# SCH_ESP32C3-haedtracker_2026-03-10.net
KiCad netlist of a schematic drawn in EasyEDA
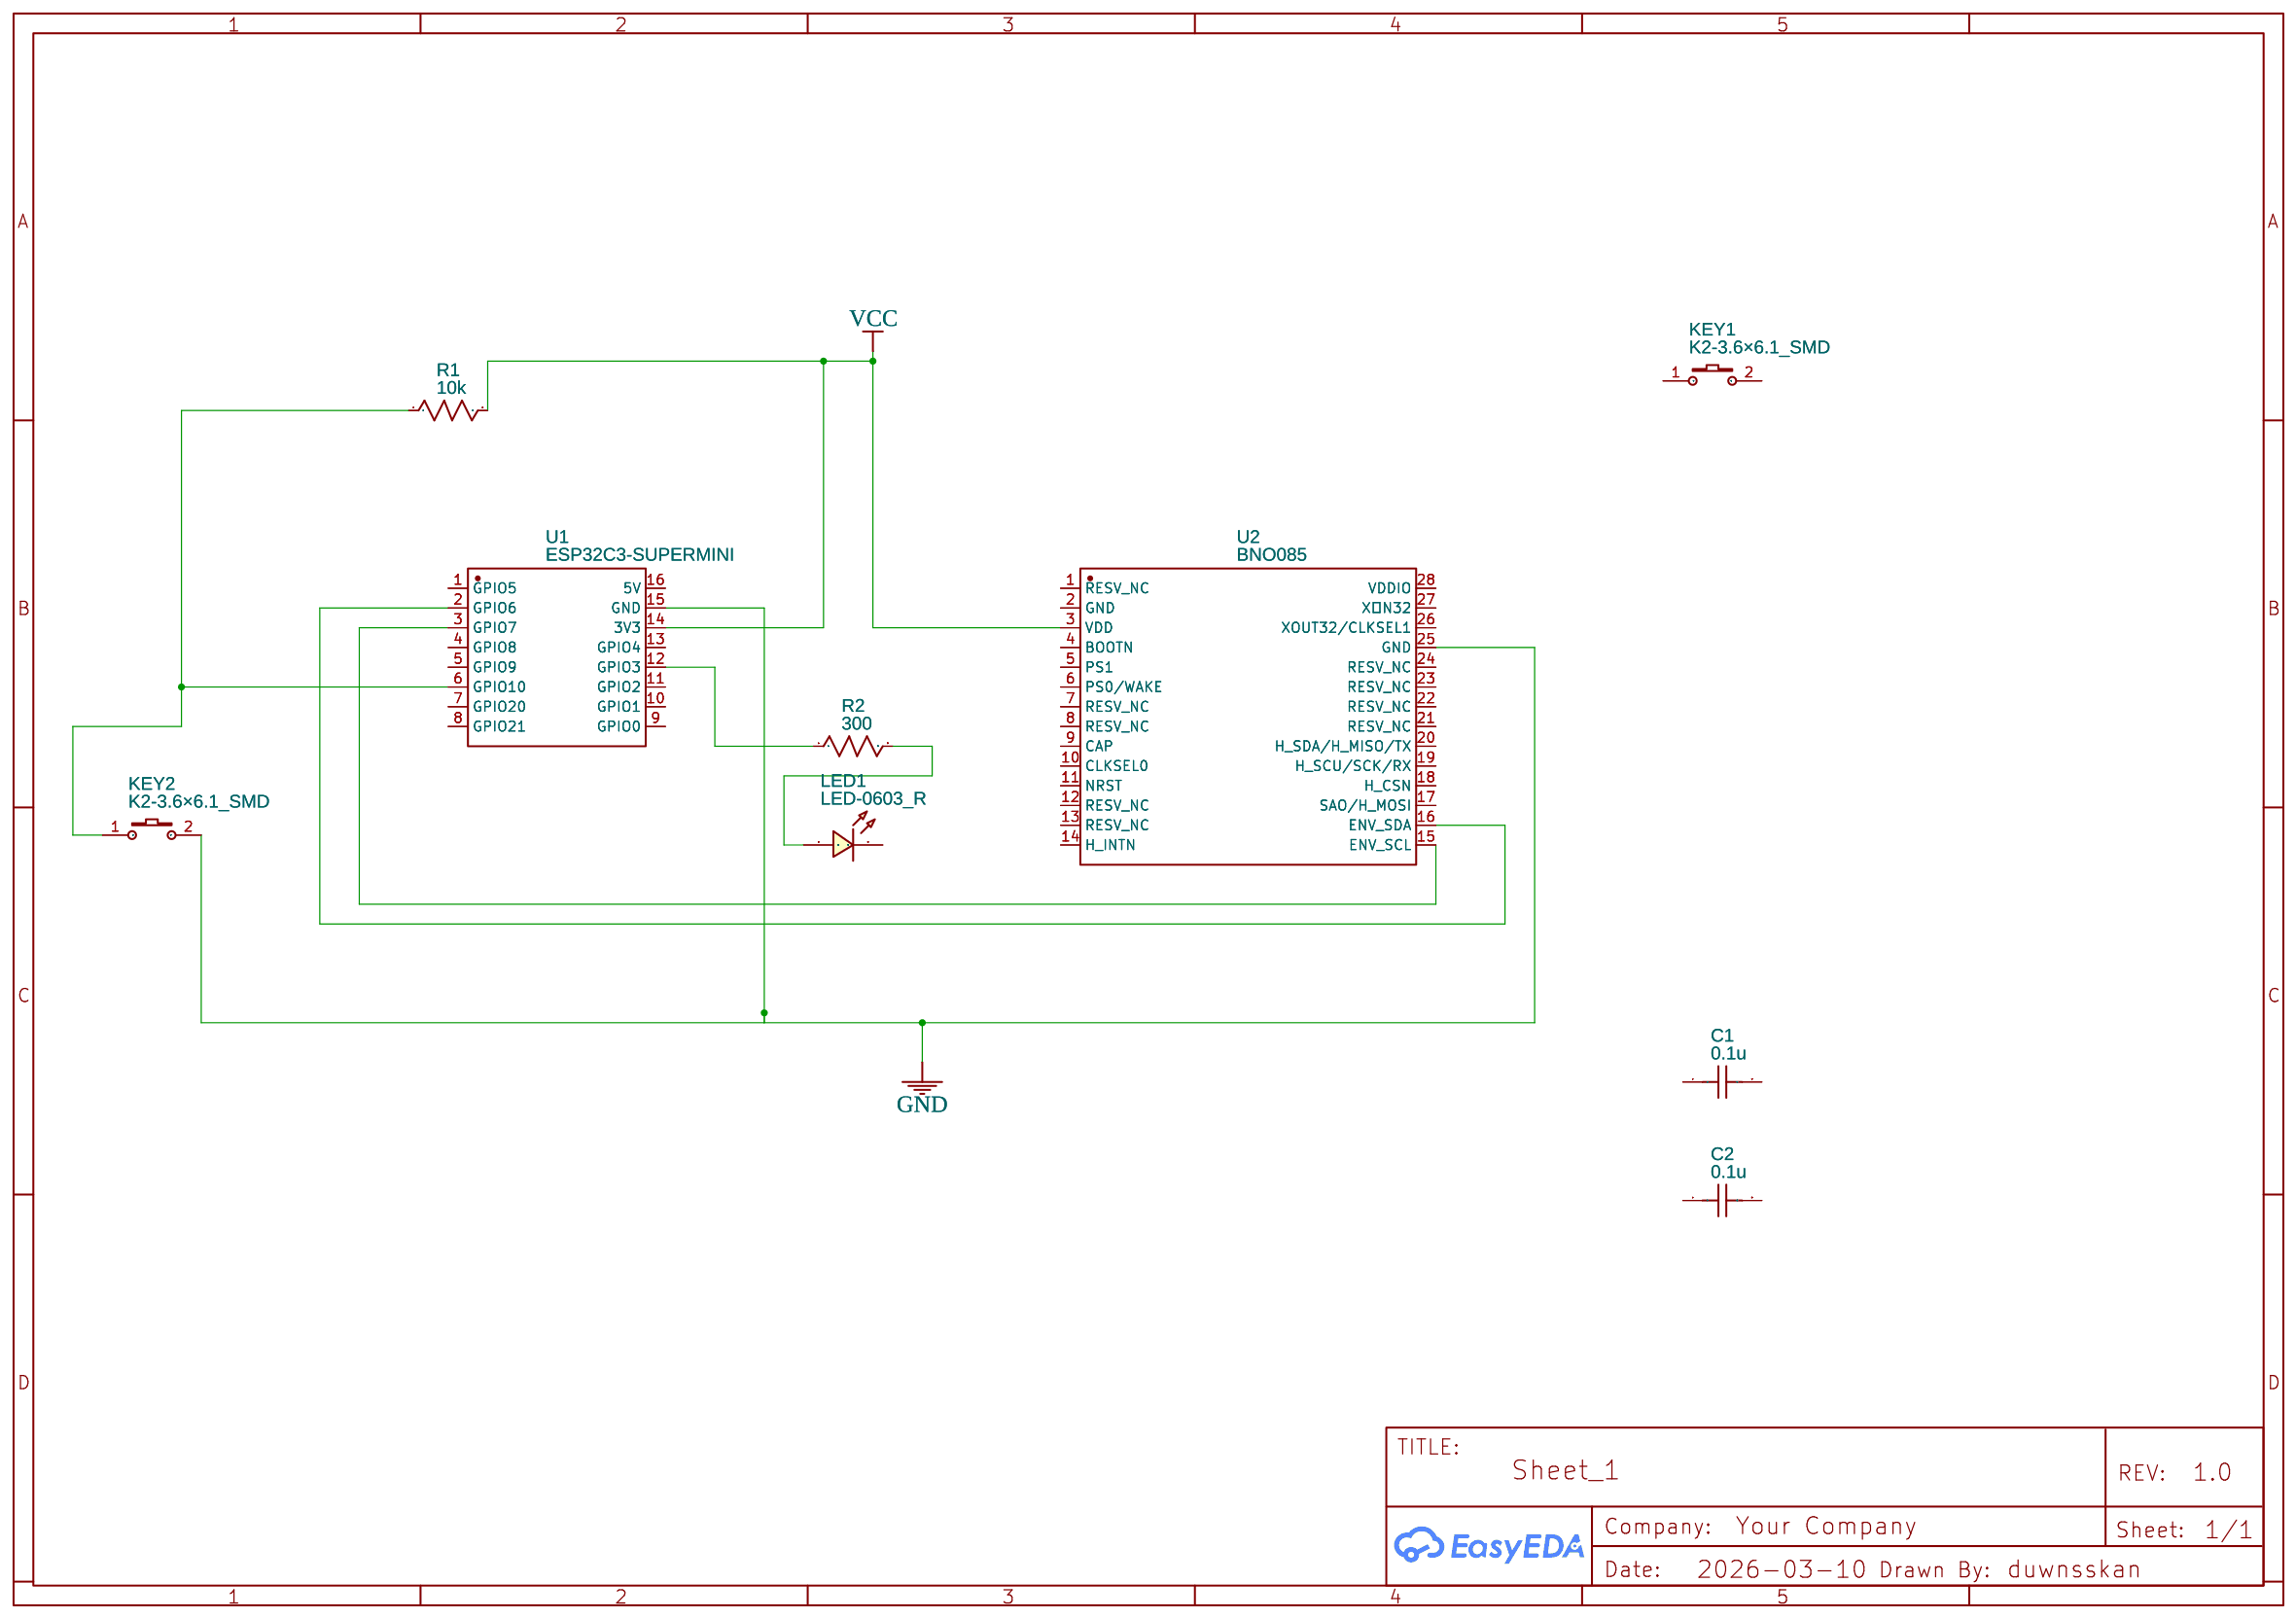
[diagram p0: schematic sheet]

(export (version "E")
  (design (tool "Eeschema 10.0.6"))
  (components
    (comp (ref "C1") (value "0.1u") (libsource (lib "") (part "C_0603_US")))
    (comp (ref "C2") (value "0.1u") (libsource (lib "") (part "C_0603_US")))
    (comp (ref "KEY1")
      (value "K2-3.6×6.1_SMD")
      (fields (field (name "Manufacturer Part") "K2-1107ST-A4SW-06"))
      (libsource (lib "") (part "K2-3.6×6.1_SMD"))
    )
    (comp (ref "KEY2")
      (value "K2-3.6×6.1_SMD")
      (fields (field (name "Manufacturer Part") "K2-1107ST-A4SW-06"))
      (libsource (lib "") (part "K2-3.6×6.1_SMD"))
    )
    (comp (ref "LED1")
      (value "LED-0603_R")
      (fields
        (field (name "Manufacturer Part") "19-217/R6C-AL1M2VY/3T")
        (field (name "Manufacturer") "EVERLIGHT(台湾亿光)")
      )
      (libsource (lib "") (part "LED-0603_R"))
    )
    (comp (ref "R1") (value "10k") (libsource (lib "") (part "R_0603_US")))
    (comp (ref "R2") (value "300") (libsource (lib "") (part "R_0603_US")))
    (comp (ref "U1")
      (value "ESP32C3-SUPERMINI")
      (fields (field (name "Manufacturer Part") "ESP32C3-SuperMini"))
      (libsource (lib "") (part "ESP32C3-SUPERMINI"))
    )
    (comp (ref "U2") (value "BNO085") (libsource (lib "") (part "BNO085")))
  )
  (nets
    (net (code "1") (name "GND") (class "Default")
      (node (ref "KEY2") (pin "2") (pinfunction "2_2") (pintype "unspecified"))
      (node (ref "U1") (pin "15") (pinfunction "GND_15") (pintype "unspecified"))
      (node (ref "U2") (pin "25") (pinfunction "GND_25") (pintype "unspecified"))
    )
    (net (code "2") (name "Net-(LED1-Pad1)") (class "Default")
      (node (ref "LED1") (pin "1") (pinfunction "1_1") (pintype "unspecified"))
      (node (ref "R2") (pin "2") (pinfunction "2_2") (pintype "unspecified"))
    )
    (net (code "3") (name "Net-(U1-GPIO3)") (class "Default")
      (node (ref "R2") (pin "1") (pinfunction "1_1") (pintype "unspecified"))
      (node (ref "U1") (pin "12") (pinfunction "GPIO3_12") (pintype "unspecified"))
    )
    (net (code "4") (name "Net-(U1-GPIO6)") (class "Default")
      (node (ref "U1") (pin "2") (pinfunction "GPIO6_2") (pintype "unspecified"))
      (node (ref "U2") (pin "16") (pinfunction "ENV_SDA_16") (pintype "unspecified"))
    )
    (net (code "5") (name "Net-(U1-GPIO7)") (class "Default")
      (node (ref "U1") (pin "3") (pinfunction "GPIO7_3") (pintype "unspecified"))
      (node (ref "U2") (pin "15") (pinfunction "ENV_SCL_15") (pintype "unspecified"))
    )
    (net (code "6") (name "Net-(U1-GPIO10)") (class "Default")
      (node (ref "KEY2") (pin "1") (pinfunction "1_1") (pintype "unspecified"))
      (node (ref "R1") (pin "1") (pinfunction "1_1") (pintype "unspecified"))
      (node (ref "U1") (pin "6") (pinfunction "GPIO10_6") (pintype "unspecified"))
    )
    (net (code "7") (name "VCC") (class "Default")
      (node (ref "R1") (pin "2") (pinfunction "2_2") (pintype "unspecified"))
      (node (ref "U1") (pin "14") (pinfunction "3V3_14") (pintype "unspecified"))
      (node (ref "U2") (pin "3") (pinfunction "VDD_3") (pintype "unspecified"))
    )
    (net (code "8") (name "unconnected-(C1-Pad1)") (class "Default")
      (node (ref "C1") (pin "1") (pinfunction "1_1") (pintype "unspecified"))
    )
    (net (code "9") (name "unconnected-(C1-Pad2)") (class "Default")
      (node (ref "C1") (pin "2") (pinfunction "2_2") (pintype "unspecified"))
    )
    (net (code "10") (name "unconnected-(C2-Pad1)") (class "Default")
      (node (ref "C2") (pin "1") (pinfunction "1_1") (pintype "unspecified"))
    )
    (net (code "11") (name "unconnected-(C2-Pad2)") (class "Default")
      (node (ref "C2") (pin "2") (pinfunction "2_2") (pintype "unspecified"))
    )
    (net (code "12") (name "unconnected-(KEY1-Pad1)") (class "Default")
      (node (ref "KEY1") (pin "1") (pinfunction "1_1") (pintype "unspecified"))
    )
    (net (code "13") (name "unconnected-(KEY1-Pad2)") (class "Default")
      (node (ref "KEY1") (pin "2") (pinfunction "2_2") (pintype "unspecified"))
    )
    (net (code "14") (name "unconnected-(LED1-Pad2)") (class "Default")
      (node (ref "LED1") (pin "2") (pinfunction "2_2") (pintype "unspecified"))
    )
    (net (code "15") (name "unconnected-(U1-5V-Pad16)") (class "Default")
      (node (ref "U1") (pin "16") (pinfunction "5V_16") (pintype "unspecified"))
    )
    (net (code "16") (name "unconnected-(U1-GPIO0-Pad9)") (class "Default")
      (node (ref "U1") (pin "9") (pinfunction "GPIO0_9") (pintype "unspecified"))
    )
    (net (code "17") (name "unconnected-(U1-GPIO1-Pad10)") (class "Default")
      (node (ref "U1") (pin "10") (pinfunction "GPIO1_10") (pintype "unspecified"))
    )
    (net (code "18") (name "unconnected-(U1-GPIO2-Pad11)") (class "Default")
      (node (ref "U1") (pin "11") (pinfunction "GPIO2_11") (pintype "unspecified"))
    )
    (net (code "19") (name "unconnected-(U1-GPIO4-Pad13)") (class "Default")
      (node (ref "U1") (pin "13") (pinfunction "GPIO4_13") (pintype "unspecified"))
    )
    (net (code "20") (name "unconnected-(U1-GPIO5-Pad1)") (class "Default")
      (node (ref "U1") (pin "1") (pinfunction "GPIO5_1") (pintype "unspecified"))
    )
    (net (code "21") (name "unconnected-(U1-GPIO8-Pad4)") (class "Default")
      (node (ref "U1") (pin "4") (pinfunction "GPIO8_4") (pintype "unspecified"))
    )
    (net (code "22") (name "unconnected-(U1-GPIO9-Pad5)") (class "Default")
      (node (ref "U1") (pin "5") (pinfunction "GPIO9_5") (pintype "unspecified"))
    )
    (net (code "23") (name "unconnected-(U1-GPIO20-Pad7)") (class "Default")
      (node (ref "U1") (pin "7") (pinfunction "GPIO20_7") (pintype "unspecified"))
    )
    (net (code "24") (name "unconnected-(U1-GPIO21-Pad8)") (class "Default")
      (node (ref "U1") (pin "8") (pinfunction "GPIO21_8") (pintype "unspecified"))
    )
    (net (code "25") (name "unconnected-(U2-BOOTN-Pad4)") (class "Default")
      (node (ref "U2") (pin "4") (pinfunction "BOOTN_4") (pintype "unspecified"))
    )
    (net (code "26") (name "unconnected-(U2-CAP-Pad9)") (class "Default")
      (node (ref "U2") (pin "9") (pinfunction "CAP_9") (pintype "unspecified"))
    )
    (net (code "27") (name "unconnected-(U2-CLKSEL0-Pad10)") (class "Default")
      (node (ref "U2") (pin "10") (pinfunction "CLKSEL0_10") (pintype "unspecified"))
    )
    (net (code "28") (name "unconnected-(U2-GND-Pad2)") (class "Default")
      (node (ref "U2") (pin "2") (pinfunction "GND_2") (pintype "unspecified"))
    )
    (net (code "29") (name "unconnected-(U2-H_CSN-Pad18)") (class "Default")
      (node (ref "U2") (pin "18") (pinfunction "H_CSN_18") (pintype "unspecified"))
    )
    (net (code "30") (name "unconnected-(U2-H_INTN-Pad14)") (class "Default")
      (node (ref "U2") (pin "14") (pinfunction "H_INTN_14") (pintype "unspecified"))
    )
    (net (code "31") (name "unconnected-(U2-H_SCU{slash}SCK{slash}RX-Pad19)") (class "Default")
      (node (ref "U2") (pin "19") (pinfunction "H_SCU/SCK/RX_19") (pintype "unspecified"))
    )
    (net (code "32") (name "unconnected-(U2-H_SDA{slash}H_MISO{slash}TX-Pad20)") (class "Default")
      (node (ref "U2") (pin "20") (pinfunction "H_SDA/H_MISO/TX_20") (pintype "unspecified"))
    )
    (net (code "33") (name "unconnected-(U2-NRST-Pad11)") (class "Default")
      (node (ref "U2") (pin "11") (pinfunction "NRST_11") (pintype "unspecified"))
    )
    (net (code "34") (name "unconnected-(U2-PS0{slash}WAKE-Pad6)") (class "Default")
      (node (ref "U2") (pin "6") (pinfunction "PS0/WAKE_6") (pintype "unspecified"))
    )
    (net (code "35") (name "unconnected-(U2-PS1-Pad5)") (class "Default")
      (node (ref "U2") (pin "5") (pinfunction "PS1_5") (pintype "unspecified"))
    )
    (net (code "36") (name "unconnected-(U2-RESV_NC-Pad1)") (class "Default")
      (node (ref "U2") (pin "1") (pinfunction "RESV_NC_1") (pintype "unspecified"))
    )
    (net (code "37") (name "unconnected-(U2-RESV_NC-Pad7)") (class "Default")
      (node (ref "U2") (pin "7") (pinfunction "RESV_NC_7") (pintype "unspecified"))
    )
    (net (code "38") (name "unconnected-(U2-RESV_NC-Pad8)") (class "Default")
      (node (ref "U2") (pin "8") (pinfunction "RESV_NC_8") (pintype "unspecified"))
    )
    (net (code "39") (name "unconnected-(U2-RESV_NC-Pad12)") (class "Default")
      (node (ref "U2") (pin "12") (pinfunction "RESV_NC_12") (pintype "unspecified"))
    )
    (net (code "40") (name "unconnected-(U2-RESV_NC-Pad13)") (class "Default")
      (node (ref "U2") (pin "13") (pinfunction "RESV_NC_13") (pintype "unspecified"))
    )
    (net (code "41") (name "unconnected-(U2-RESV_NC-Pad21)") (class "Default")
      (node (ref "U2") (pin "21") (pinfunction "RESV_NC_21") (pintype "unspecified"))
    )
    (net (code "42") (name "unconnected-(U2-RESV_NC-Pad22)") (class "Default")
      (node (ref "U2") (pin "22") (pinfunction "RESV_NC_22") (pintype "unspecified"))
    )
    (net (code "43") (name "unconnected-(U2-RESV_NC-Pad23)") (class "Default")
      (node (ref "U2") (pin "23") (pinfunction "RESV_NC_23") (pintype "unspecified"))
    )
    (net (code "44") (name "unconnected-(U2-RESV_NC-Pad24)") (class "Default")
      (node (ref "U2") (pin "24") (pinfunction "RESV_NC_24") (pintype "unspecified"))
    )
    (net (code "45") (name "unconnected-(U2-SAO{slash}H_MOSI-Pad17)") (class "Default")
      (node (ref "U2") (pin "17") (pinfunction "SAO/H_MOSI_17") (pintype "unspecified"))
    )
    (net (code "46") (name "unconnected-(U2-VDDIO-Pad28)") (class "Default")
      (node (ref "U2") (pin "28") (pinfunction "VDDIO_28") (pintype "unspecified"))
    )
    (net (code "47") (name "unconnected-(U2-XOUT32{slash}CLKSEL1-Pad26)") (class "Default")
      (node (ref "U2") (pin "26") (pinfunction "XOUT32/CLKSEL1_26") (pintype "unspecified"))
    )
    (net (code "48") (name "unconnected-(U2-XⅪN32-Pad27)") (class "Default")
      (node (ref "U2") (pin "27") (pinfunction "XⅪN32_27") (pintype "unspecified"))
    )
  )
)
